# Current_measurement.net
KiCad netlist of a schematic drawn in Altium Designer
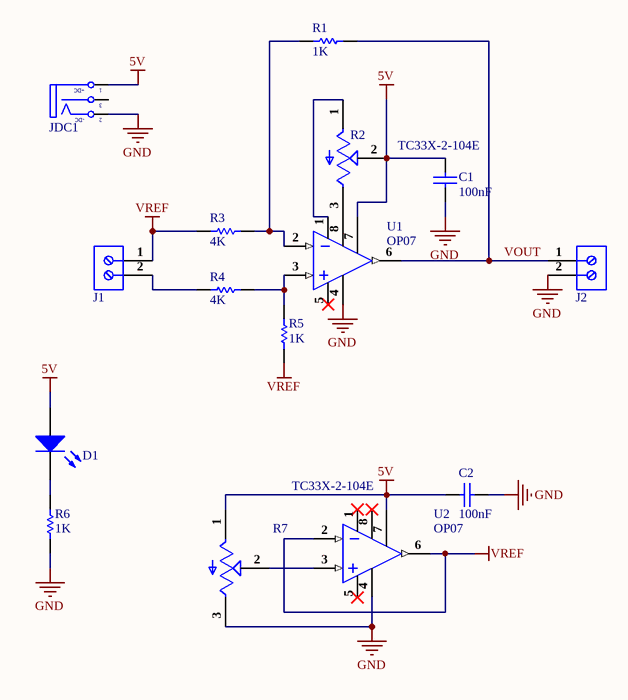
[diagram p0: Current_measurement.SchDoc]

(export (version "E")
  (design (tool "Eeschema 10.0.6"))
  (components
    (comp (ref "C1")
      (value "100nF")
      (footprint "CAP-SM-0805")
      (description "Capacitor")
      (fields (field (name "Comment") "Cap Non-Pol SMD"))
      (libsource (lib "PIF_Library") (part "Cap Non-Pol SMD"))
    )
    (comp (ref "C2")
      (value "100nF")
      (footprint "CAP-SM-0805")
      (description "Capacitor")
      (fields (field (name "Comment") "Cap Non-Pol SMD"))
      (libsource (lib "PIF_Library") (part "Cap Non-Pol SMD"))
    )
    (comp (ref "D1")
      (value "LED SMD")
      (footprint "LED_0805_Blue")
      (description "LED")
      (libsource (lib "PIF_Library") (part "LED SMD"))
    )
    (comp (ref "J1")
      (value "691214300002")
      (footprint "691214300002")
      (description "WR-TBL Series 2143 Vertical Entry Modular, Through Hole, pitch 3.81mm, 2p")
      (fields (field (name "MANUFACTURER") "Wurth Elektronik"))
      (libsource (lib "Altium_WR-TBL (rev22a)") (part "691214300002"))
    )
    (comp (ref "J2")
      (value "691214300002")
      (footprint "691214300002")
      (description "WR-TBL Series 2143 Vertical Entry Modular, Through Hole, pitch 3.81mm, 2p")
      (fields (field (name "MANUFACTURER") "Wurth Elektronik"))
      (libsource (lib "Altium_WR-TBL (rev22a)") (part "691214300002"))
    )
    (comp (ref "JDC1")
      (value "Jack DC")
      (footprint "DC-IN")
      (description "Jack DC input")
      (libsource (lib "PIF_Library") (part "Jack DC"))
    )
    (comp (ref "R1")
      (value "1K")
      (footprint "RES-SM-0805")
      (description "Resistor")
      (fields (field (name "Comment") "RESISTOR SMD"))
      (libsource (lib "PIF_Library") (part "RESISTOR SMD"))
    )
    (comp (ref "R2")
      (value "TC33X-2-104E")
      (footprint "TRIM_TC33X-2-104E")
      (description "100 kOhms 0.1W, 1/10W J Lead Surface Mount Trimmer Potentiometer Cermet 1 Turn Top Adjustment")
      (fields (field (name "MF") "Bourns"))
      (libsource (lib "TC33X-2-104E") (part "TC33X-2-104E"))
    )
    (comp (ref "R3")
      (value "4K")
      (footprint "RES-SM-0805")
      (description "Resistor")
      (fields (field (name "Comment") "RESISTOR SMD"))
      (libsource (lib "PIF_Library") (part "RESISTOR SMD"))
    )
    (comp (ref "R4")
      (value "4K")
      (footprint "RES-SM-0805")
      (description "Resistor")
      (fields (field (name "Comment") "RESISTOR SMD"))
      (libsource (lib "PIF_Library") (part "RESISTOR SMD"))
    )
    (comp (ref "R5")
      (value "1K")
      (footprint "RES-SM-0805")
      (description "Resistor")
      (fields (field (name "Comment") "RESISTOR SMD"))
      (libsource (lib "PIF_Library") (part "RESISTOR SMD"))
    )
    (comp (ref "R6")
      (value "1K")
      (footprint "RES-SM-0805")
      (description "Resistor")
      (fields (field (name "Comment") "RESISTOR SMD"))
      (libsource (lib "PIF_Library") (part "RESISTOR SMD"))
    )
    (comp (ref "R7")
      (value "TC33X-2-104E")
      (footprint "TRIM_TC33X-2-104E")
      (description "100 kOhms 0.1W, 1/10W J Lead Surface Mount Trimmer Potentiometer Cermet 1 Turn Top Adjustment")
      (fields (field (name "MF") "Bourns"))
      (libsource (lib "TC33X-2-104E") (part "TC33X-2-104E"))
    )
    (comp (ref "U1") (value "OP07") (footprint "SOIC8-OP07") (libsource (lib "YenDoo") (part "OP07")))
    (comp (ref "U2") (value "OP07") (footprint "SOIC8-OP07") (libsource (lib "YenDoo") (part "OP07")))
  )
  (nets
    (net (code "1") (name "/VOUT") (class "Default")
      (node (ref "J2") (pin "1") (pinfunction "1_1") (pintype "passive"))
      (node (ref "R1") (pin "2") (pinfunction "2_2") (pintype "passive"))
      (node (ref "U1") (pin "6") (pinfunction "OUT_6") (pintype "output"))
    )
    (net (code "2") (name "5V") (class "Default")
      (node (ref "C1") (pin "2") (pinfunction "2_2") (pintype "passive"))
      (node (ref "C2") (pin "2") (pinfunction "2_2") (pintype "passive"))
      (node (ref "D1") (pin "1") (pinfunction "A_1") (pintype "passive"))
      (node (ref "JDC1") (pin "1") (pinfunction "T_1") (pintype "passive"))
      (node (ref "R2") (pin "2") (pinfunction "W_2") (pintype "passive"))
      (node (ref "R7") (pin "1") (pinfunction "CCW_1") (pintype "passive"))
      (node (ref "U1") (pin "7") (pinfunction "+V_7") (pintype "passive"))
      (node (ref "U2") (pin "7") (pinfunction "+V_7") (pintype "passive"))
    )
    (net (code "3") (name "GND") (class "Default")
      (node (ref "C1") (pin "1") (pinfunction "1_1") (pintype "passive"))
      (node (ref "C2") (pin "1") (pinfunction "1_1") (pintype "passive"))
      (node (ref "J2") (pin "2") (pinfunction "2_2") (pintype "passive"))
      (node (ref "JDC1") (pin "2") (pinfunction "TN_2") (pintype "passive"))
      (node (ref "R6") (pin "2") (pinfunction "2_2") (pintype "passive"))
      (node (ref "R7") (pin "3") (pinfunction "CW_3") (pintype "passive"))
      (node (ref "U1") (pin "4") (pinfunction "-V_4") (pintype "passive"))
      (node (ref "U2") (pin "4") (pinfunction "-V_4") (pintype "passive"))
    )
    (net (code "4") (name "Net-(D1-K)") (class "Default")
      (node (ref "D1") (pin "2") (pinfunction "K_2") (pintype "passive"))
      (node (ref "R6") (pin "1") (pinfunction "1_1") (pintype "passive"))
    )
    (net (code "5") (name "Net-(J1-Pad2)") (class "Default")
      (node (ref "J1") (pin "2") (pinfunction "2_2") (pintype "passive"))
      (node (ref "R4") (pin "1") (pinfunction "1_1") (pintype "passive"))
    )
    (net (code "6") (name "Net-(R2-CCW)") (class "Default")
      (node (ref "R2") (pin "1") (pinfunction "CCW_1") (pintype "passive"))
      (node (ref "U1") (pin "1") (pinfunction "NULL_1") (pintype "passive"))
    )
    (net (code "7") (name "Net-(R2-CW)") (class "Default")
      (node (ref "R2") (pin "3") (pinfunction "CW_3") (pintype "passive"))
      (node (ref "U1") (pin "8") (pinfunction "NULL_8") (pintype "passive"))
    )
    (net (code "8") (name "Net-(R7-W)") (class "Default")
      (node (ref "R7") (pin "2") (pinfunction "W_2") (pintype "passive"))
      (node (ref "U2") (pin "3") (pinfunction "IN+_3") (pintype "input"))
    )
    (net (code "9") (name "Net-(U1-IN+)") (class "Default")
      (node (ref "R4") (pin "2") (pinfunction "2_2") (pintype "passive"))
      (node (ref "R5") (pin "1") (pinfunction "1_1") (pintype "passive"))
      (node (ref "U1") (pin "3") (pinfunction "IN+_3") (pintype "input"))
    )
    (net (code "10") (name "Net-(U1-IN-)") (class "Default")
      (node (ref "R1") (pin "1") (pinfunction "1_1") (pintype "passive"))
      (node (ref "R3") (pin "2") (pinfunction "2_2") (pintype "passive"))
      (node (ref "U1") (pin "2") (pinfunction "IN-_2") (pintype "input"))
    )
    (net (code "11") (name "VREF") (class "Default")
      (node (ref "J1") (pin "1") (pinfunction "1_1") (pintype "passive"))
      (node (ref "R3") (pin "1") (pinfunction "1_1") (pintype "passive"))
      (node (ref "R5") (pin "2") (pinfunction "2_2") (pintype "passive"))
      (node (ref "U2") (pin "2") (pinfunction "IN-_2") (pintype "input"))
      (node (ref "U2") (pin "6") (pinfunction "OUT_6") (pintype "output"))
    )
    (net (code "12") (name "unconnected-(JDC1-S-Pad3)") (class "Default")
      (node (ref "JDC1") (pin "3") (pinfunction "S_3") (pintype "power_in"))
    )
    (net (code "13") (name "unconnected-(U1-Pad5)") (class "Default")
      (node (ref "U1") (pin "5") (pinfunction "5_5") (pintype "passive+no_connect"))
    )
    (net (code "14") (name "unconnected-(U2-NULL-Pad1)") (class "Default")
      (node (ref "U2") (pin "1") (pinfunction "NULL_1") (pintype "passive+no_connect"))
    )
    (net (code "15") (name "unconnected-(U2-NULL-Pad8)") (class "Default")
      (node (ref "U2") (pin "8") (pinfunction "NULL_8") (pintype "passive+no_connect"))
    )
    (net (code "16") (name "unconnected-(U2-Pad5)") (class "Default")
      (node (ref "U2") (pin "5") (pinfunction "5_5") (pintype "passive+no_connect"))
    )
  )
)
